# ProtoCAT_wireless.net
KiCad netlist of a schematic drawn in EAGLE
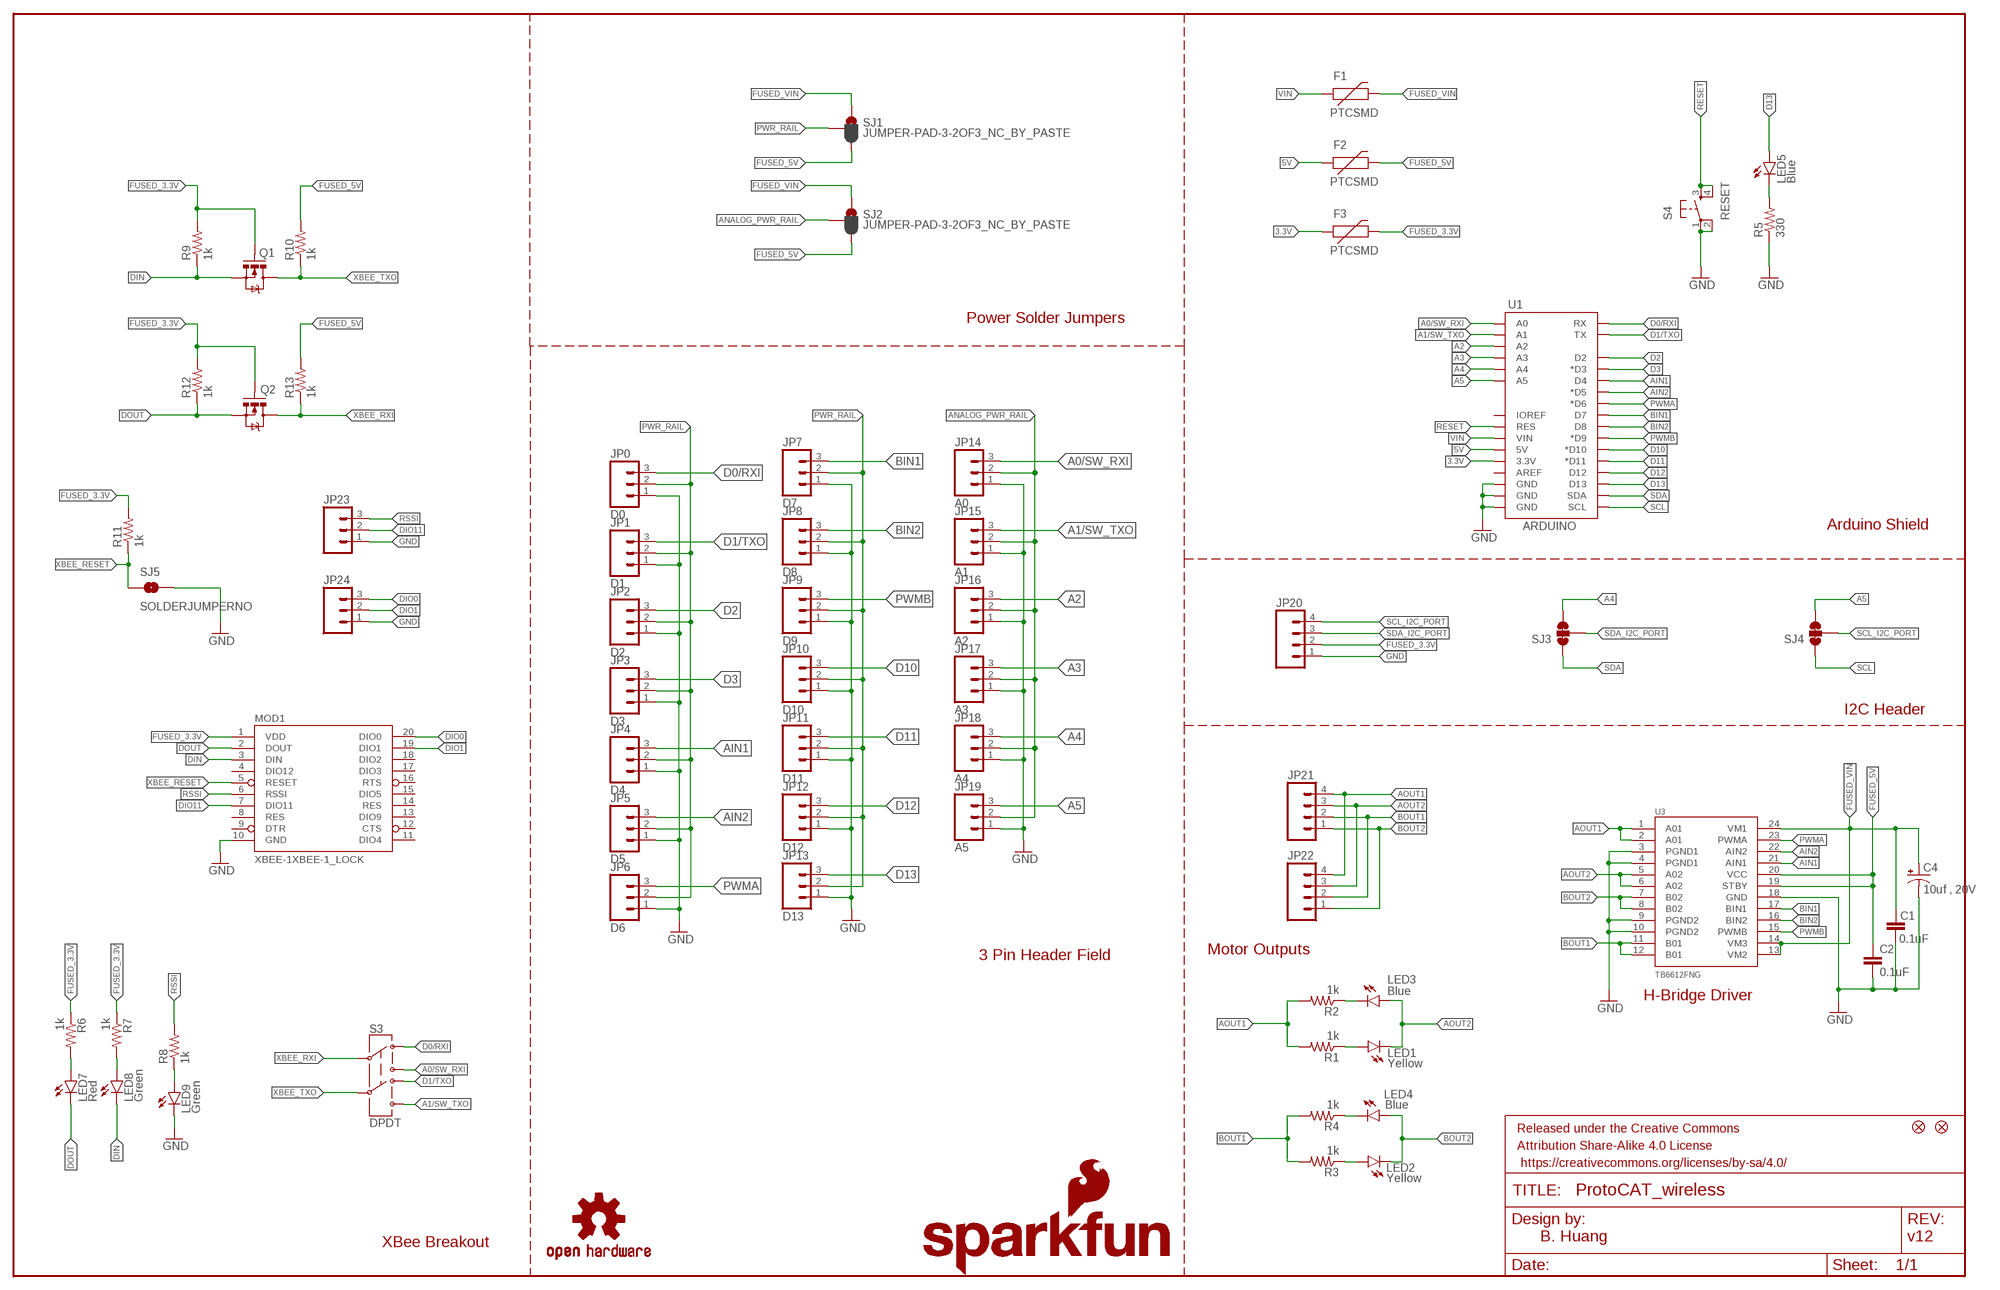
[diagram p0: schematic, sheet 1]

(export (version "E")
  (design (tool "Eeschema 10.0.6"))
  (components
    (comp (ref "C1")
      (value "0.1uF")
      (footprint "eagle-import:0603-CAP")
      (libsource (lib "eagle-import") (part "0.1UF-25V-5%(0603)"))
    )
    (comp (ref "C2")
      (value "0.1uF")
      (footprint "eagle-import:0603-CAP")
      (libsource (lib "eagle-import") (part "0.1UF-25V-5%(0603)"))
    )
    (comp (ref "C4")
      (value "10uf , 20V")
      (footprint "eagle-import:EIA3528")
      (libsource (lib "eagle-import") (part "10UF-20V-10%(TANT)"))
    )
    (comp (ref "F1")
      (value "PTCSMD")
      (footprint "eagle-import:PTC-1206")
      (libsource (lib "eagle-import") (part "PTCSMD"))
    )
    (comp (ref "F2")
      (value "PTCSMD")
      (footprint "eagle-import:PTC-1206")
      (libsource (lib "eagle-import") (part "PTCSMD"))
    )
    (comp (ref "F3")
      (value "PTCSMD")
      (footprint "eagle-import:PTC-1206")
      (libsource (lib "eagle-import") (part "PTCSMD"))
    )
    (comp (ref "FID1")
      (value "FIDUCIAL1X2")
      (footprint "eagle-import:FIDUCIAL-1X2")
      (libsource (lib "eagle-import") (part "FIDUCIAL1X2"))
    )
    (comp (ref "FID2")
      (value "FIDUCIAL1X2")
      (footprint "eagle-import:FIDUCIAL-1X2")
      (libsource (lib "eagle-import") (part "FIDUCIAL1X2"))
    )
    (comp (ref "FRAME1")
      (value "FRAME-LEDGER")
      (footprint "eagle-import:CREATIVE_COMMONS")
      (libsource (lib "eagle-import") (part "FRAME-LEDGER"))
    )
    (comp (ref "JP0")
      (value "D0")
      (footprint "eagle-import:1X03_LOCK")
      (libsource (lib "eagle-import") (part "M03LOCK"))
    )
    (comp (ref "JP1")
      (value "D1")
      (footprint "eagle-import:1X03_LOCK")
      (libsource (lib "eagle-import") (part "M03LOCK"))
    )
    (comp (ref "JP2")
      (value "D2")
      (footprint "eagle-import:1X03_LOCK")
      (libsource (lib "eagle-import") (part "M03LOCK"))
    )
    (comp (ref "JP3")
      (value "D3")
      (footprint "eagle-import:1X03_LOCK")
      (libsource (lib "eagle-import") (part "M03LOCK"))
    )
    (comp (ref "JP4")
      (value "D4")
      (footprint "eagle-import:1X03_LOCK")
      (libsource (lib "eagle-import") (part "M03LOCK"))
    )
    (comp (ref "JP5")
      (value "D5")
      (footprint "eagle-import:1X03_LOCK")
      (libsource (lib "eagle-import") (part "M03LOCK"))
    )
    (comp (ref "JP6")
      (value "D6")
      (footprint "eagle-import:1X03_LOCK")
      (libsource (lib "eagle-import") (part "M03LOCK"))
    )
    (comp (ref "JP7")
      (value "D7")
      (footprint "eagle-import:1X03_LOCK")
      (libsource (lib "eagle-import") (part "M03LOCK"))
    )
    (comp (ref "JP8")
      (value "D8")
      (footprint "eagle-import:1X03_LOCK")
      (libsource (lib "eagle-import") (part "M03LOCK"))
    )
    (comp (ref "JP9")
      (value "D9")
      (footprint "eagle-import:1X03_LOCK")
      (libsource (lib "eagle-import") (part "M03LOCK"))
    )
    (comp (ref "JP10")
      (value "D10")
      (footprint "eagle-import:1X03_LOCK")
      (libsource (lib "eagle-import") (part "M03LOCK"))
    )
    (comp (ref "JP11")
      (value "D11")
      (footprint "eagle-import:1X03_LOCK")
      (libsource (lib "eagle-import") (part "M03LOCK"))
    )
    (comp (ref "JP12")
      (value "D12")
      (footprint "eagle-import:1X03_LOCK")
      (libsource (lib "eagle-import") (part "M03LOCK"))
    )
    (comp (ref "JP13")
      (value "D13")
      (footprint "eagle-import:1X03_LOCK")
      (libsource (lib "eagle-import") (part "M03LOCK"))
    )
    (comp (ref "JP14")
      (value "A0")
      (footprint "eagle-import:1X03_LOCK")
      (libsource (lib "eagle-import") (part "M03LOCK"))
    )
    (comp (ref "JP15")
      (value "A1")
      (footprint "eagle-import:1X03_LOCK")
      (libsource (lib "eagle-import") (part "M03LOCK"))
    )
    (comp (ref "JP16")
      (value "A2")
      (footprint "eagle-import:1X03_LOCK")
      (libsource (lib "eagle-import") (part "M03LOCK"))
    )
    (comp (ref "JP17")
      (value "A3")
      (footprint "eagle-import:1X03_LOCK")
      (libsource (lib "eagle-import") (part "M03LOCK"))
    )
    (comp (ref "JP18")
      (value "A4")
      (footprint "eagle-import:1X03_LOCK")
      (libsource (lib "eagle-import") (part "M03LOCK"))
    )
    (comp (ref "JP19")
      (value "A5")
      (footprint "eagle-import:1X03_LOCK")
      (libsource (lib "eagle-import") (part "M03LOCK"))
    )
    (comp (ref "JP20")
      (value "M04PTH")
      (footprint "eagle-import:1X04")
      (libsource (lib "eagle-import") (part "M04PTH"))
    )
    (comp (ref "JP21")
      (value "M04PTH")
      (footprint "eagle-import:1X04")
      (libsource (lib "eagle-import") (part "M04PTH"))
    )
    (comp (ref "JP22")
      (value "M04SMD_STRAIGHT_COMBO")
      (footprint "eagle-import:1X04_SMD_STRAIGHT_COMBO")
      (libsource (lib "eagle-import") (part "M04SMD_STRAIGHT_COMBO"))
    )
    (comp (ref "JP23")
      (value "M031X03_NO_SILK")
      (footprint "eagle-import:1X03_NO_SILK")
      (libsource (lib "eagle-import") (part "M031X03_NO_SILK"))
    )
    (comp (ref "JP24")
      (value "M031X03_NO_SILK")
      (footprint "eagle-import:1X03_NO_SILK")
      (libsource (lib "eagle-import") (part "M031X03_NO_SILK"))
    )
    (comp (ref "LED1")
      (value "Yellow")
      (footprint "eagle-import:LED-0603")
      (libsource (lib "eagle-import") (part "LED0603"))
    )
    (comp (ref "LED2")
      (value "Yellow")
      (footprint "eagle-import:LED-0603")
      (libsource (lib "eagle-import") (part "LED0603"))
    )
    (comp (ref "LED3")
      (value "Blue")
      (footprint "eagle-import:LED-0603")
      (libsource (lib "eagle-import") (part "LED0603"))
    )
    (comp (ref "LED4")
      (value "Blue")
      (footprint "eagle-import:LED-0603")
      (libsource (lib "eagle-import") (part "LED0603"))
    )
    (comp (ref "LED5")
      (value "Blue")
      (footprint "eagle-import:LED-0603")
      (libsource (lib "eagle-import") (part "LED0603"))
    )
    (comp (ref "LED7")
      (value "Red")
      (footprint "eagle-import:LED-0603")
      (libsource (lib "eagle-import") (part "LED-RED0603"))
    )
    (comp (ref "LED8")
      (value "Green")
      (footprint "eagle-import:LED-0603")
      (libsource (lib "eagle-import") (part "LED-GREEN0603"))
    )
    (comp (ref "LED9")
      (value "Green")
      (footprint "eagle-import:LED-0603")
      (libsource (lib "eagle-import") (part "LED-GREEN0603"))
    )
    (comp (ref "LOGO1")
      (value "OSHW-LOGOM")
      (footprint "eagle-import:OSHW-LOGO-M")
      (libsource (lib "eagle-import") (part "OSHW-LOGOM"))
    )
    (comp (ref "LOGO2")
      (value "SFE_LOGO_NAME_FLAME.1_INCH")
      (footprint "eagle-import:SFE_LOGO_NAME_FLAME_.1")
      (libsource (lib "eagle-import") (part "SFE_LOGO_NAME_FLAME.1_INCH"))
    )
    (comp (ref "LOGO3")
      (value "SFE_LOGO_FLAME.2COP")
      (footprint "eagle-import:SFE_LOGO_FLAME_COPPER_.2")
      (libsource (lib "eagle-import") (part "SFE_LOGO_FLAME.2COP"))
    )
    (comp (ref "LOGO4")
      (value "SFE_LOGO_NAME_FLAME.1_INCH")
      (footprint "eagle-import:SFE_LOGO_NAME_FLAME_.1")
      (libsource (lib "eagle-import") (part "SFE_LOGO_NAME_FLAME.1_INCH"))
    )
    (comp (ref "MOD1")
      (value "XBEE-1XBEE-1_LOCK")
      (footprint "eagle-import:XBEE-1_LOCK")
      (libsource (lib "eagle-import") (part "XBEE-1XBEE-1_LOCK"))
    )
    (comp (ref "Q1")
      (value "MOSFET-NCHANNELSMD")
      (footprint "eagle-import:SOT23-3")
      (libsource (lib "eagle-import") (part "MOSFET-NCHANNELSMD"))
    )
    (comp (ref "Q2")
      (value "MOSFET-NCHANNELSMD")
      (footprint "eagle-import:SOT23-3")
      (libsource (lib "eagle-import") (part "MOSFET-NCHANNELSMD"))
    )
    (comp (ref "R1")
      (value "1k")
      (footprint "eagle-import:0603-RES")
      (libsource (lib "eagle-import") (part "1KOHM1/10W1%(0603)"))
    )
    (comp (ref "R2")
      (value "1k")
      (footprint "eagle-import:0603-RES")
      (libsource (lib "eagle-import") (part "1KOHM1/10W1%(0603)"))
    )
    (comp (ref "R3")
      (value "1k")
      (footprint "eagle-import:0603-RES")
      (libsource (lib "eagle-import") (part "1KOHM1/10W1%(0603)"))
    )
    (comp (ref "R4")
      (value "1k")
      (footprint "eagle-import:0603-RES")
      (libsource (lib "eagle-import") (part "1KOHM1/10W1%(0603)"))
    )
    (comp (ref "R5")
      (value "330")
      (footprint "eagle-import:0603-RES")
      (libsource (lib "eagle-import") (part "330OHM1/10W1%(0603)"))
    )
    (comp (ref "R6")
      (value "1k")
      (footprint "eagle-import:0603-RES")
      (libsource (lib "eagle-import") (part "1KOHM1/10W1%(0603)"))
    )
    (comp (ref "R7")
      (value "1k")
      (footprint "eagle-import:0603-RES")
      (libsource (lib "eagle-import") (part "1KOHM1/10W1%(0603)"))
    )
    (comp (ref "R8")
      (value "1k")
      (footprint "eagle-import:0603-RES")
      (libsource (lib "eagle-import") (part "1KOHM1/10W1%(0603)"))
    )
    (comp (ref "R9")
      (value "1k")
      (footprint "eagle-import:0603-RES")
      (libsource (lib "eagle-import") (part "1KOHM1/10W1%(0603)"))
    )
    (comp (ref "R10")
      (value "1k")
      (footprint "eagle-import:0603-RES")
      (libsource (lib "eagle-import") (part "1KOHM1/10W1%(0603)"))
    )
    (comp (ref "R11")
      (value "1k")
      (footprint "eagle-import:0603-RES")
      (libsource (lib "eagle-import") (part "1KOHM1/10W1%(0603)"))
    )
    (comp (ref "R12")
      (value "1k")
      (footprint "eagle-import:0603-RES")
      (libsource (lib "eagle-import") (part "1KOHM1/10W1%(0603)"))
    )
    (comp (ref "R13")
      (value "1k")
      (footprint "eagle-import:0603-RES")
      (libsource (lib "eagle-import") (part "1KOHM1/10W1%(0603)"))
    )
    (comp (ref "S3")
      (value "DPDT")
      (footprint "eagle-import:AYZ0202")
      (fields (field (name "PROD_ID") "SWCH-08179"))
      (libsource (lib "eagle-import") (part "SWITCH-DPDTAYZ0202"))
    )
    (comp (ref "S4")
      (value "RESET")
      (footprint "eagle-import:TACTILE-SWITCH-SMD")
      (libsource (lib "eagle-import") (part "TAC_SWITCHSMD"))
    )
    (comp (ref "SJ1")
      (value "JUMPER-PAD-3-2OF3_NC_BY_PASTE")
      (footprint "eagle-import:PAD-JUMPER-3-2OF3_NC_BY_PASTE_YES_SILK_FULL_BOX")
      (libsource (lib "eagle-import") (part "JUMPER-PAD-3-2OF3_NC_BY_PASTE"))
    )
    (comp (ref "SJ2")
      (value "JUMPER-PAD-3-2OF3_NC_BY_PASTE")
      (footprint "eagle-import:PAD-JUMPER-3-2OF3_NC_BY_PASTE_YES_SILK_FULL_BOX")
      (libsource (lib "eagle-import") (part "JUMPER-PAD-3-2OF3_NC_BY_PASTE"))
    )
    (comp (ref "SJ3")
      (value "JUMPER-PAD-3-NC_BY_TRACE")
      (footprint "eagle-import:PAD-JUMPER-3-3OF3_NC_BY_TRACE_YES_SILK_FULL_BOX")
      (libsource (lib "eagle-import") (part "JUMPER-PAD-3-NC_BY_TRACE"))
    )
    (comp (ref "SJ4")
      (value "JUMPER-PAD-3-NC_BY_TRACE")
      (footprint "eagle-import:PAD-JUMPER-3-3OF3_NC_BY_TRACE_YES_SILK_FULL_BOX")
      (libsource (lib "eagle-import") (part "JUMPER-PAD-3-NC_BY_TRACE"))
    )
    (comp (ref "SJ5")
      (value "SOLDERJUMPERNO")
      (footprint "eagle-import:SJ_2S-NO")
      (libsource (lib "eagle-import") (part "SOLDERJUMPERNO"))
    )
    (comp (ref "U$1")
      (value "SFE_LUDUS")
      (footprint "eagle-import:SFE_LUDUS-M")
      (libsource (lib "eagle-import") (part "SFE_LUDUS"))
    )
    (comp (ref "U1")
      (value "ARDUINO")
      (footprint "eagle-import:UNO_R3_SHIELD_NOLABELS")
      (libsource (lib "eagle-import") (part "ARDUINO_R3_SHIELDNOLABELS"))
    )
    (comp (ref "U3")
      (value "TB6612FNG")
      (footprint "eagle-import:SSOP24")
      (libsource (lib "eagle-import") (part "TB6612FNG"))
    )
  )
  (nets
    (net (code "1") (name "3.3V") (class "Default")
      (node (ref "F3") (pin "1") (pinfunction "1_1") (pintype "bidirectional"))
      (node (ref "U1") (pin "3.3V") (pinfunction "3.3V_3.3V") (pintype "bidirectional"))
    )
    (net (code "2") (name "5V") (class "Default")
      (node (ref "F2") (pin "1") (pinfunction "1_1") (pintype "bidirectional"))
      (node (ref "U1") (pin "5V") (pinfunction "5V_5V") (pintype "bidirectional"))
    )
    (net (code "3") (name "A0{slash}SW_RXI") (class "Default")
      (node (ref "JP14") (pin "3") (pinfunction "3_3") (pintype "passive"))
      (node (ref "S3") (pin "3") (pinfunction "3_3") (pintype "bidirectional"))
      (node (ref "U1") (pin "A0") (pinfunction "A0_A0") (pintype "bidirectional"))
    )
    (net (code "4") (name "A1{slash}SW_TXO") (class "Default")
      (node (ref "JP15") (pin "3") (pinfunction "3_3") (pintype "passive"))
      (node (ref "S3") (pin "6") (pinfunction "6_6") (pintype "bidirectional"))
      (node (ref "U1") (pin "A1") (pinfunction "A1_A1") (pintype "bidirectional"))
    )
    (net (code "5") (name "A2") (class "Default")
      (node (ref "JP16") (pin "3") (pinfunction "3_3") (pintype "passive"))
      (node (ref "U1") (pin "A2") (pinfunction "A2_A2") (pintype "bidirectional"))
    )
    (net (code "6") (name "A3") (class "Default")
      (node (ref "JP17") (pin "3") (pinfunction "3_3") (pintype "passive"))
      (node (ref "U1") (pin "A3") (pinfunction "A3_A3") (pintype "bidirectional"))
    )
    (net (code "7") (name "A4") (class "Default")
      (node (ref "JP18") (pin "3") (pinfunction "3_3") (pintype "passive"))
      (node (ref "SJ3") (pin "3") (pinfunction "3_3") (pintype "passive"))
      (node (ref "U1") (pin "A4") (pinfunction "A4_A4") (pintype "bidirectional"))
    )
    (net (code "8") (name "A5") (class "Default")
      (node (ref "JP19") (pin "3") (pinfunction "3_3") (pintype "passive"))
      (node (ref "SJ4") (pin "3") (pinfunction "3_3") (pintype "passive"))
      (node (ref "U1") (pin "A5") (pinfunction "A5_A5") (pintype "bidirectional"))
    )
    (net (code "9") (name "AIN1") (class "Default")
      (node (ref "JP4") (pin "3") (pinfunction "3_3") (pintype "passive"))
      (node (ref "U1") (pin "D4") (pinfunction "D4_D4") (pintype "bidirectional"))
      (node (ref "U3") (pin "21") (pinfunction "AIN1_21") (pintype "bidirectional"))
    )
    (net (code "10") (name "AIN2") (class "Default")
      (node (ref "JP5") (pin "3") (pinfunction "3_3") (pintype "passive"))
      (node (ref "U1") (pin "D5") (pinfunction "*D5_D5") (pintype "bidirectional"))
      (node (ref "U3") (pin "22") (pinfunction "AIN2_22") (pintype "bidirectional"))
    )
    (net (code "11") (name "ANALOG_PWR_RAIL") (class "Default")
      (node (ref "JP14") (pin "2") (pinfunction "2_2") (pintype "passive"))
      (node (ref "JP15") (pin "2") (pinfunction "2_2") (pintype "passive"))
      (node (ref "JP16") (pin "2") (pinfunction "2_2") (pintype "passive"))
      (node (ref "JP17") (pin "2") (pinfunction "2_2") (pintype "passive"))
      (node (ref "JP18") (pin "2") (pinfunction "2_2") (pintype "passive"))
      (node (ref "JP19") (pin "2") (pinfunction "2_2") (pintype "passive"))
      (node (ref "SJ2") (pin "2") (pinfunction "2_2") (pintype "passive"))
    )
    (net (code "12") (name "AOUT1") (class "Default")
      (node (ref "JP21") (pin "4") (pinfunction "4_4") (pintype "passive"))
      (node (ref "JP22") (pin "4") (pinfunction "4_4") (pintype "passive"))
      (node (ref "R1") (pin "2") (pinfunction "2_2") (pintype "passive"))
      (node (ref "R2") (pin "2") (pinfunction "2_2") (pintype "passive"))
      (node (ref "U3") (pin "1") (pinfunction "A01_1") (pintype "bidirectional"))
      (node (ref "U3") (pin "2") (pinfunction "A01_2") (pintype "bidirectional"))
    )
    (net (code "13") (name "AOUT2") (class "Default")
      (node (ref "JP21") (pin "3") (pinfunction "3_3") (pintype "passive"))
      (node (ref "JP22") (pin "3") (pinfunction "3_3") (pintype "passive"))
      (node (ref "LED1") (pin "C") (pinfunction "C_C") (pintype "passive"))
      (node (ref "LED3") (pin "A") (pinfunction "A_A") (pintype "passive"))
      (node (ref "U3") (pin "5") (pinfunction "A02_5") (pintype "bidirectional"))
      (node (ref "U3") (pin "6") (pinfunction "A02_6") (pintype "bidirectional"))
    )
    (net (code "14") (name "BIN1") (class "Default")
      (node (ref "JP7") (pin "3") (pinfunction "3_3") (pintype "passive"))
      (node (ref "U1") (pin "D7") (pinfunction "D7_D7") (pintype "bidirectional"))
      (node (ref "U3") (pin "17") (pinfunction "BIN1_17") (pintype "bidirectional"))
    )
    (net (code "15") (name "BIN2") (class "Default")
      (node (ref "JP8") (pin "3") (pinfunction "3_3") (pintype "passive"))
      (node (ref "U1") (pin "D8") (pinfunction "D8_D8") (pintype "bidirectional"))
      (node (ref "U3") (pin "16") (pinfunction "BIN2_16") (pintype "bidirectional"))
    )
    (net (code "16") (name "BOUT1") (class "Default")
      (node (ref "JP21") (pin "2") (pinfunction "2_2") (pintype "passive"))
      (node (ref "JP22") (pin "2") (pinfunction "2_2") (pintype "passive"))
      (node (ref "R3") (pin "2") (pinfunction "2_2") (pintype "passive"))
      (node (ref "R4") (pin "2") (pinfunction "2_2") (pintype "passive"))
      (node (ref "U3") (pin "11") (pinfunction "B01_11") (pintype "bidirectional"))
      (node (ref "U3") (pin "12") (pinfunction "B01_12") (pintype "bidirectional"))
    )
    (net (code "17") (name "BOUT2") (class "Default")
      (node (ref "JP21") (pin "1") (pinfunction "1_1") (pintype "passive"))
      (node (ref "JP22") (pin "1") (pinfunction "1_1") (pintype "passive"))
      (node (ref "LED2") (pin "C") (pinfunction "C_C") (pintype "passive"))
      (node (ref "LED4") (pin "A") (pinfunction "A_A") (pintype "passive"))
      (node (ref "U3") (pin "7") (pinfunction "B02_7") (pintype "bidirectional"))
      (node (ref "U3") (pin "8") (pinfunction "B02_8") (pintype "bidirectional"))
    )
    (net (code "18") (name "D0{slash}RXI") (class "Default")
      (node (ref "JP0") (pin "3") (pinfunction "3_3") (pintype "passive"))
      (node (ref "S3") (pin "1") (pinfunction "1_1") (pintype "bidirectional"))
      (node (ref "U1") (pin "RX") (pinfunction "RX_RX") (pintype "bidirectional"))
    )
    (net (code "19") (name "D1{slash}TXO") (class "Default")
      (node (ref "JP1") (pin "3") (pinfunction "3_3") (pintype "passive"))
      (node (ref "S3") (pin "4") (pinfunction "4_4") (pintype "bidirectional"))
      (node (ref "U1") (pin "TX") (pinfunction "TX_TX") (pintype "bidirectional"))
    )
    (net (code "20") (name "D2") (class "Default")
      (node (ref "JP2") (pin "3") (pinfunction "3_3") (pintype "passive"))
      (node (ref "U1") (pin "D2") (pinfunction "D2_D2") (pintype "bidirectional"))
    )
    (net (code "21") (name "D3") (class "Default")
      (node (ref "JP3") (pin "3") (pinfunction "3_3") (pintype "passive"))
      (node (ref "U1") (pin "D3") (pinfunction "*D3_D3") (pintype "bidirectional"))
    )
    (net (code "22") (name "D10") (class "Default")
      (node (ref "JP10") (pin "3") (pinfunction "3_3") (pintype "passive"))
      (node (ref "U1") (pin "D10") (pinfunction "*D10_D10") (pintype "bidirectional"))
    )
    (net (code "23") (name "D11") (class "Default")
      (node (ref "JP11") (pin "3") (pinfunction "3_3") (pintype "passive"))
      (node (ref "U1") (pin "D11") (pinfunction "*D11_D11") (pintype "bidirectional"))
    )
    (net (code "24") (name "D12") (class "Default")
      (node (ref "JP12") (pin "3") (pinfunction "3_3") (pintype "passive"))
      (node (ref "U1") (pin "D12") (pinfunction "D12_D12") (pintype "bidirectional"))
    )
    (net (code "25") (name "D13") (class "Default")
      (node (ref "JP13") (pin "3") (pinfunction "3_3") (pintype "passive"))
      (node (ref "LED5") (pin "A") (pinfunction "A_A") (pintype "passive"))
      (node (ref "U1") (pin "D13") (pinfunction "D13_D13") (pintype "bidirectional"))
    )
    (net (code "26") (name "DIN") (class "Default")
      (node (ref "LED8") (pin "C") (pinfunction "C_C") (pintype "passive"))
      (node (ref "MOD1") (pin "3") (pinfunction "DIN_3") (pintype "input"))
      (node (ref "Q1") (pin "2") (pinfunction "S_2") (pintype "passive"))
      (node (ref "R9") (pin "1") (pinfunction "1_1") (pintype "passive"))
    )
    (net (code "27") (name "DIO0") (class "Default")
      (node (ref "JP24") (pin "3") (pinfunction "3_3") (pintype "passive"))
      (node (ref "MOD1") (pin "20") (pinfunction "DIO0_20") (pintype "bidirectional"))
    )
    (net (code "28") (name "DIO1") (class "Default")
      (node (ref "JP24") (pin "2") (pinfunction "2_2") (pintype "passive"))
      (node (ref "MOD1") (pin "19") (pinfunction "DIO1_19") (pintype "bidirectional"))
    )
    (net (code "29") (name "DIO11") (class "Default")
      (node (ref "JP23") (pin "2") (pinfunction "2_2") (pintype "passive"))
      (node (ref "MOD1") (pin "7") (pinfunction "DIO11_7") (pintype "bidirectional"))
    )
    (net (code "30") (name "DOUT") (class "Default")
      (node (ref "LED7") (pin "C") (pinfunction "C_C") (pintype "passive"))
      (node (ref "MOD1") (pin "2") (pinfunction "DOUT_2") (pintype "output"))
      (node (ref "Q2") (pin "2") (pinfunction "S_2") (pintype "passive"))
      (node (ref "R12") (pin "1") (pinfunction "1_1") (pintype "passive"))
    )
    (net (code "31") (name "FUSED_3.3V") (class "Default")
      (node (ref "F3") (pin "2") (pinfunction "2_2") (pintype "bidirectional"))
      (node (ref "JP20") (pin "2") (pinfunction "2_2") (pintype "passive"))
      (node (ref "MOD1") (pin "1") (pinfunction "VDD_1") (pintype "power_in"))
      (node (ref "Q1") (pin "1") (pinfunction "G_1") (pintype "passive"))
      (node (ref "Q2") (pin "1") (pinfunction "G_1") (pintype "passive"))
      (node (ref "R11") (pin "2") (pinfunction "2_2") (pintype "passive"))
      (node (ref "R12") (pin "2") (pinfunction "2_2") (pintype "passive"))
      (node (ref "R6") (pin "1") (pinfunction "1_1") (pintype "passive"))
      (node (ref "R7") (pin "1") (pinfunction "1_1") (pintype "passive"))
      (node (ref "R9") (pin "2") (pinfunction "2_2") (pintype "passive"))
    )
    (net (code "32") (name "FUSED_5V") (class "Default")
      (node (ref "C2") (pin "1") (pinfunction "1_1") (pintype "passive"))
      (node (ref "F2") (pin "2") (pinfunction "2_2") (pintype "bidirectional"))
      (node (ref "R10") (pin "2") (pinfunction "2_2") (pintype "passive"))
      (node (ref "R13") (pin "2") (pinfunction "2_2") (pintype "passive"))
      (node (ref "SJ1") (pin "3") (pinfunction "3_3") (pintype "passive"))
      (node (ref "SJ2") (pin "3") (pinfunction "3_3") (pintype "passive"))
      (node (ref "U3") (pin "19") (pinfunction "STBY_19") (pintype "bidirectional"))
      (node (ref "U3") (pin "20") (pinfunction "VCC_20") (pintype "bidirectional"))
    )
    (net (code "33") (name "FUSED_VIN") (class "Default")
      (node (ref "C1") (pin "1") (pinfunction "1_1") (pintype "passive"))
      (node (ref "C4") (pin "A") (pinfunction "+_A") (pintype "passive"))
      (node (ref "F1") (pin "2") (pinfunction "2_2") (pintype "bidirectional"))
      (node (ref "SJ1") (pin "1") (pinfunction "1_1") (pintype "passive"))
      (node (ref "SJ2") (pin "1") (pinfunction "1_1") (pintype "passive"))
      (node (ref "U3") (pin "13") (pinfunction "VM2_13") (pintype "bidirectional"))
      (node (ref "U3") (pin "14") (pinfunction "VM3_14") (pintype "bidirectional"))
      (node (ref "U3") (pin "24") (pinfunction "VM1_24") (pintype "bidirectional"))
    )
    (net (code "34") (name "GND") (class "Default")
      (node (ref "C1") (pin "2") (pinfunction "2_2") (pintype "passive"))
      (node (ref "C2") (pin "2") (pinfunction "2_2") (pintype "passive"))
      (node (ref "C4") (pin "C") (pinfunction "-_C") (pintype "passive"))
      (node (ref "JP0") (pin "1") (pinfunction "1_1") (pintype "passive"))
      (node (ref "JP1") (pin "1") (pinfunction "1_1") (pintype "passive"))
      (node (ref "JP10") (pin "1") (pinfunction "1_1") (pintype "passive"))
      (node (ref "JP11") (pin "1") (pinfunction "1_1") (pintype "passive"))
      (node (ref "JP12") (pin "1") (pinfunction "1_1") (pintype "passive"))
      (node (ref "JP13") (pin "1") (pinfunction "1_1") (pintype "passive"))
      (node (ref "JP14") (pin "1") (pinfunction "1_1") (pintype "passive"))
      (node (ref "JP15") (pin "1") (pinfunction "1_1") (pintype "passive"))
      (node (ref "JP16") (pin "1") (pinfunction "1_1") (pintype "passive"))
      (node (ref "JP17") (pin "1") (pinfunction "1_1") (pintype "passive"))
      (node (ref "JP18") (pin "1") (pinfunction "1_1") (pintype "passive"))
      (node (ref "JP19") (pin "1") (pinfunction "1_1") (pintype "passive"))
      (node (ref "JP2") (pin "1") (pinfunction "1_1") (pintype "passive"))
      (node (ref "JP20") (pin "1") (pinfunction "1_1") (pintype "passive"))
      (node (ref "JP23") (pin "1") (pinfunction "1_1") (pintype "passive"))
      (node (ref "JP24") (pin "1") (pinfunction "1_1") (pintype "passive"))
      (node (ref "JP3") (pin "1") (pinfunction "1_1") (pintype "passive"))
      (node (ref "JP4") (pin "1") (pinfunction "1_1") (pintype "passive"))
      (node (ref "JP5") (pin "1") (pinfunction "1_1") (pintype "passive"))
      (node (ref "JP6") (pin "1") (pinfunction "1_1") (pintype "passive"))
      (node (ref "JP7") (pin "1") (pinfunction "1_1") (pintype "passive"))
      (node (ref "JP8") (pin "1") (pinfunction "1_1") (pintype "passive"))
      (node (ref "JP9") (pin "1") (pinfunction "1_1") (pintype "passive"))
      (node (ref "LED9") (pin "C") (pinfunction "C_C") (pintype "passive"))
      (node (ref "MOD1") (pin "10") (pinfunction "GND_10") (pintype "power_in"))
      (node (ref "R5") (pin "1") (pinfunction "1_1") (pintype "passive"))
      (node (ref "S4") (pin "1") (pinfunction "1_1") (pintype "passive"))
      (node (ref "S4") (pin "2") (pinfunction "2_2") (pintype "passive"))
      (node (ref "SJ5") (pin "2") (pinfunction "2_2") (pintype "passive"))
      (node (ref "U1") (pin "GND@0") (pinfunction "GND_GND@0") (pintype "bidirectional"))
      (node (ref "U1") (pin "GND@1") (pinfunction "GND_GND@1") (pintype "bidirectional"))
      (node (ref "U1") (pin "GND@2") (pinfunction "GND_GND@2") (pintype "bidirectional"))
      (node (ref "U3") (pin "10") (pinfunction "PGND2_10") (pintype "bidirectional"))
      (node (ref "U3") (pin "18") (pinfunction "GND_18") (pintype "bidirectional"))
      (node (ref "U3") (pin "3") (pinfunction "PGND1_3") (pintype "bidirectional"))
      (node (ref "U3") (pin "4") (pinfunction "PGND1_4") (pintype "bidirectional"))
      (node (ref "U3") (pin "9") (pinfunction "PGND2_9") (pintype "bidirectional"))
    )
    (net (code "35") (name "Net-(LED1-PadA)") (class "Default")
      (node (ref "LED1") (pin "A") (pinfunction "A_A") (pintype "passive"))
      (node (ref "R1") (pin "1") (pinfunction "1_1") (pintype "passive"))
    )
    (net (code "36") (name "Net-(LED2-PadA)") (class "Default")
      (node (ref "LED2") (pin "A") (pinfunction "A_A") (pintype "passive"))
      (node (ref "R3") (pin "1") (pinfunction "1_1") (pintype "passive"))
    )
    (net (code "37") (name "Net-(LED3-PadC)") (class "Default")
      (node (ref "LED3") (pin "C") (pinfunction "C_C") (pintype "passive"))
      (node (ref "R2") (pin "1") (pinfunction "1_1") (pintype "passive"))
    )
    (net (code "38") (name "Net-(LED4-PadC)") (class "Default")
      (node (ref "LED4") (pin "C") (pinfunction "C_C") (pintype "passive"))
      (node (ref "R4") (pin "1") (pinfunction "1_1") (pintype "passive"))
    )
    (net (code "39") (name "Net-(LED5-PadC)") (class "Default")
      (node (ref "LED5") (pin "C") (pinfunction "C_C") (pintype "passive"))
      (node (ref "R5") (pin "2") (pinfunction "2_2") (pintype "passive"))
    )
    (net (code "40") (name "Net-(LED7-PadA)") (class "Default")
      (node (ref "LED7") (pin "A") (pinfunction "A_A") (pintype "passive"))
      (node (ref "R6") (pin "2") (pinfunction "2_2") (pintype "passive"))
    )
    (net (code "41") (name "Net-(LED8-PadA)") (class "Default")
      (node (ref "LED8") (pin "A") (pinfunction "A_A") (pintype "passive"))
      (node (ref "R7") (pin "2") (pinfunction "2_2") (pintype "passive"))
    )
    (net (code "42") (name "Net-(LED9-PadA)") (class "Default")
      (node (ref "LED9") (pin "A") (pinfunction "A_A") (pintype "passive"))
      (node (ref "R8") (pin "1") (pinfunction "1_1") (pintype "passive"))
    )
    (net (code "43") (name "PWMA") (class "Default")
      (node (ref "JP6") (pin "3") (pinfunction "3_3") (pintype "passive"))
      (node (ref "U1") (pin "D6") (pinfunction "*D6_D6") (pintype "bidirectional"))
      (node (ref "U3") (pin "23") (pinfunction "PWMA_23") (pintype "bidirectional"))
    )
    (net (code "44") (name "PWMB") (class "Default")
      (node (ref "JP9") (pin "3") (pinfunction "3_3") (pintype "passive"))
      (node (ref "U1") (pin "D9") (pinfunction "*D9_D9") (pintype "bidirectional"))
      (node (ref "U3") (pin "15") (pinfunction "PWMB_15") (pintype "bidirectional"))
    )
    (net (code "45") (name "PWR_RAIL") (class "Default")
      (node (ref "JP0") (pin "2") (pinfunction "2_2") (pintype "passive"))
      (node (ref "JP1") (pin "2") (pinfunction "2_2") (pintype "passive"))
      (node (ref "JP10") (pin "2") (pinfunction "2_2") (pintype "passive"))
      (node (ref "JP11") (pin "2") (pinfunction "2_2") (pintype "passive"))
      (node (ref "JP12") (pin "2") (pinfunction "2_2") (pintype "passive"))
      (node (ref "JP13") (pin "2") (pinfunction "2_2") (pintype "passive"))
      (node (ref "JP2") (pin "2") (pinfunction "2_2") (pintype "passive"))
      (node (ref "JP3") (pin "2") (pinfunction "2_2") (pintype "passive"))
      (node (ref "JP4") (pin "2") (pinfunction "2_2") (pintype "passive"))
      (node (ref "JP5") (pin "2") (pinfunction "2_2") (pintype "passive"))
      (node (ref "JP6") (pin "2") (pinfunction "2_2") (pintype "passive"))
      (node (ref "JP7") (pin "2") (pinfunction "2_2") (pintype "passive"))
      (node (ref "JP8") (pin "2") (pinfunction "2_2") (pintype "passive"))
      (node (ref "JP9") (pin "2") (pinfunction "2_2") (pintype "passive"))
      (node (ref "SJ1") (pin "2") (pinfunction "2_2") (pintype "passive"))
    )
    (net (code "46") (name "RESET") (class "Default")
      (node (ref "S4") (pin "3") (pinfunction "3_3") (pintype "passive"))
      (node (ref "S4") (pin "4") (pinfunction "4_4") (pintype "passive"))
      (node (ref "U1") (pin "RES") (pinfunction "RES_RES") (pintype "bidirectional"))
    )
    (net (code "47") (name "RSSI") (class "Default")
      (node (ref "JP23") (pin "3") (pinfunction "3_3") (pintype "passive"))
      (node (ref "MOD1") (pin "6") (pinfunction "RSSI_6") (pintype "bidirectional"))
      (node (ref "R8") (pin "2") (pinfunction "2_2") (pintype "passive"))
    )
    (net (code "48") (name "SCL") (class "Default")
      (node (ref "SJ4") (pin "1") (pinfunction "1_1") (pintype "passive"))
      (node (ref "U1") (pin "SCL") (pinfunction "SCL_SCL") (pintype "bidirectional"))
    )
    (net (code "49") (name "SCL_I2C_PORT") (class "Default")
      (node (ref "JP20") (pin "4") (pinfunction "4_4") (pintype "passive"))
      (node (ref "SJ4") (pin "2") (pinfunction "2_2") (pintype "passive"))
    )
    (net (code "50") (name "SDA") (class "Default")
      (node (ref "SJ3") (pin "1") (pinfunction "1_1") (pintype "passive"))
      (node (ref "U1") (pin "SDA") (pinfunction "SDA_SDA") (pintype "bidirectional"))
    )
    (net (code "51") (name "SDA_I2C_PORT") (class "Default")
      (node (ref "JP20") (pin "3") (pinfunction "3_3") (pintype "passive"))
      (node (ref "SJ3") (pin "2") (pinfunction "2_2") (pintype "passive"))
    )
    (net (code "52") (name "VIN") (class "Default")
      (node (ref "F1") (pin "1") (pinfunction "1_1") (pintype "bidirectional"))
      (node (ref "U1") (pin "VIN") (pinfunction "VIN_VIN") (pintype "bidirectional"))
    )
    (net (code "53") (name "XBEE_RESET") (class "Default")
      (node (ref "MOD1") (pin "5") (pinfunction "RESET_5") (pintype "input"))
      (node (ref "R11") (pin "1") (pinfunction "1_1") (pintype "passive"))
      (node (ref "SJ5") (pin "1") (pinfunction "1_1") (pintype "passive"))
    )
    (net (code "54") (name "XBEE_RXI") (class "Default")
      (node (ref "Q2") (pin "3") (pinfunction "D_3") (pintype "passive"))
      (node (ref "R13") (pin "1") (pinfunction "1_1") (pintype "passive"))
      (node (ref "S3") (pin "2") (pinfunction "2_2") (pintype "bidirectional"))
    )
    (net (code "55") (name "XBEE_TXO") (class "Default")
      (node (ref "Q1") (pin "3") (pinfunction "D_3") (pintype "passive"))
      (node (ref "R10") (pin "1") (pinfunction "1_1") (pintype "passive"))
      (node (ref "S3") (pin "5") (pinfunction "5_5") (pintype "bidirectional"))
    )
    (net (code "56") (name "unconnected-(MOD1-CTS-Pad12)") (class "Default")
      (node (ref "MOD1") (pin "12") (pinfunction "CTS_12") (pintype "output"))
    )
    (net (code "57") (name "unconnected-(MOD1-DIO2-Pad18)") (class "Default")
      (node (ref "MOD1") (pin "18") (pinfunction "DIO2_18") (pintype "bidirectional"))
    )
    (net (code "58") (name "unconnected-(MOD1-DIO3-Pad17)") (class "Default")
      (node (ref "MOD1") (pin "17") (pinfunction "DIO3_17") (pintype "bidirectional"))
    )
    (net (code "59") (name "unconnected-(MOD1-DIO4-Pad11)") (class "Default")
      (node (ref "MOD1") (pin "11") (pinfunction "DIO4_11") (pintype "bidirectional"))
    )
    (net (code "60") (name "unconnected-(MOD1-DIO5-Pad15)") (class "Default")
      (node (ref "MOD1") (pin "15") (pinfunction "DIO5_15") (pintype "bidirectional"))
    )
    (net (code "61") (name "unconnected-(MOD1-DIO9-Pad13)") (class "Default")
      (node (ref "MOD1") (pin "13") (pinfunction "DIO9_13") (pintype "bidirectional"))
    )
    (net (code "62") (name "unconnected-(MOD1-DIO12-Pad4)") (class "Default")
      (node (ref "MOD1") (pin "4") (pinfunction "DIO12_4") (pintype "bidirectional"))
    )
    (net (code "63") (name "unconnected-(MOD1-DTR-Pad9)") (class "Default")
      (node (ref "MOD1") (pin "9") (pinfunction "DTR_9") (pintype "bidirectional"))
    )
    (net (code "64") (name "unconnected-(MOD1-RES-Pad8)") (class "Default")
      (node (ref "MOD1") (pin "8") (pinfunction "RES_8") (pintype "bidirectional"))
    )
    (net (code "65") (name "unconnected-(MOD1-RES-Pad14)") (class "Default")
      (node (ref "MOD1") (pin "14") (pinfunction "RES_14") (pintype "bidirectional"))
    )
    (net (code "66") (name "unconnected-(MOD1-RTS-Pad16)") (class "Default")
      (node (ref "MOD1") (pin "16") (pinfunction "RTS_16") (pintype "input"))
    )
    (net (code "67") (name "unconnected-(U1-PadAREF)") (class "Default")
      (node (ref "U1") (pin "AREF") (pinfunction "AREF_AREF") (pintype "bidirectional"))
    )
    (net (code "68") (name "unconnected-(U1-PadIOREF)") (class "Default")
      (node (ref "U1") (pin "IOREF") (pinfunction "IOREF_IOREF") (pintype "bidirectional"))
    )
  )
)
